# I2C_MULTIPLEX.net
KiCad netlist of a schematic drawn in Altium Designer
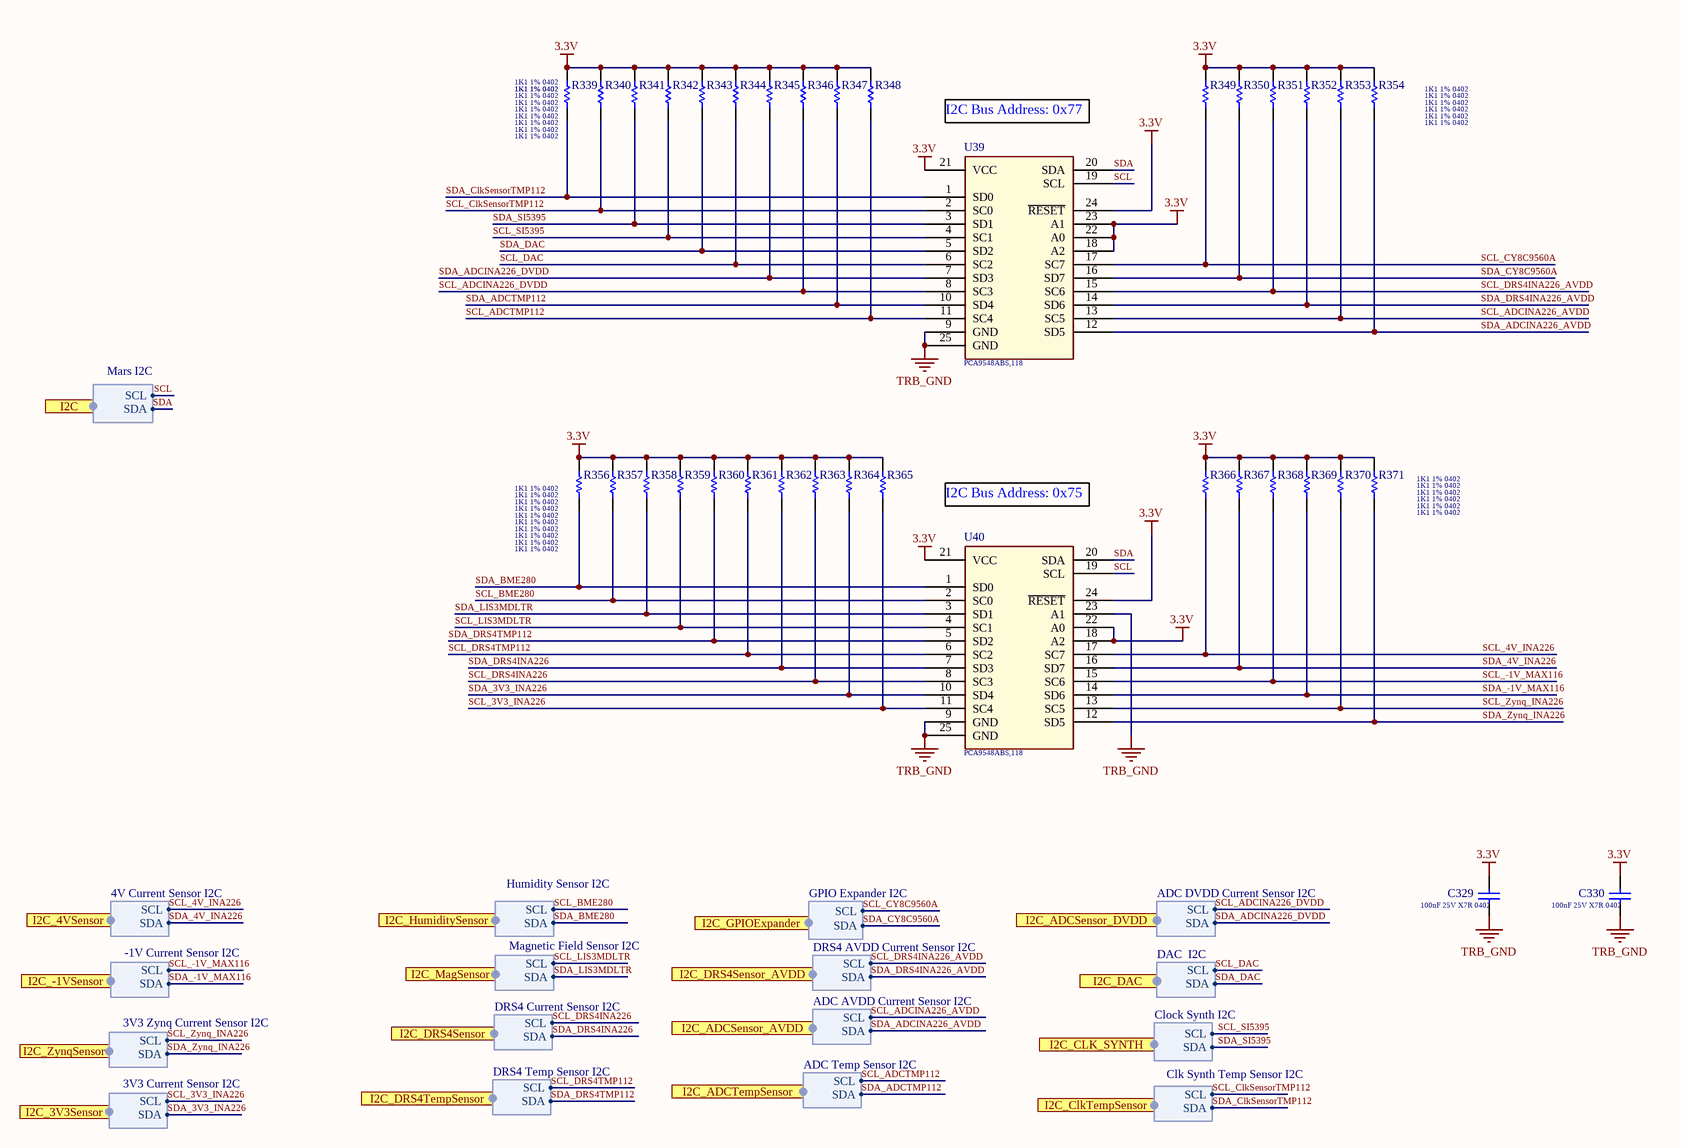
[diagram p0: I2C_MULTIPLEX.SchDoc]

(export (version "E")
  (design (tool "Eeschema 10.0.6"))
  (components
    (comp (ref "C329")
      (value "Cap_Taiyo_Yuden_TMK105B7104KV-FR_100nF")
      (footprint "Cap_Taiyo_Yuden_TMK105B7104KV-FR_100nF")
      (description "CAP CER 100nF 25V X7R 0402")
      (fields (field (name "CAPACITANCE") "100nF 25V X7R 0402"))
      (libsource (lib "Cap_Taiyo_Yuden_TMK105B7104KV-FR_100nF") (part "Cap_Taiyo_Yuden_TMK105B7104KV-FR_100nF"))
    )
    (comp (ref "C330")
      (value "Cap_Taiyo_Yuden_TMK105B7104KV-FR_100nF")
      (footprint "Cap_Taiyo_Yuden_TMK105B7104KV-FR_100nF")
      (description "CAP CER 100nF 25V X7R 0402")
      (fields (field (name "CAPACITANCE") "100nF 25V X7R 0402"))
      (libsource (lib "Cap_Taiyo_Yuden_TMK105B7104KV-FR_100nF") (part "Cap_Taiyo_Yuden_TMK105B7104KV-FR_100nF"))
    )
    (comp (ref "R339")
      (value "1K1 1% 0402")
      (footprint "RESC0402(1005)_L")
      (description "1K1 0.063W 1% 0402 (1005 Metric)  SMD")
      (fields (field (name "POWER") "0.063 W") (field (name "TOLERANCE") "1 %"))
      (libsource (lib "Altium Content Vault") (part "RES"))
    )
    (comp (ref "R340")
      (value "1K1 1% 0402")
      (footprint "RESC0402(1005)_L")
      (description "1K1 0.063W 1% 0402 (1005 Metric)  SMD")
      (fields (field (name "POWER") "0.063 W") (field (name "TOLERANCE") "1 %"))
      (libsource (lib "Altium Content Vault") (part "RES"))
    )
    (comp (ref "R341")
      (value "1K1 1% 0402")
      (footprint "RESC0402(1005)_L")
      (description "1K1 0.063W 1% 0402 (1005 Metric)  SMD")
      (fields (field (name "POWER") "0.063 W") (field (name "TOLERANCE") "1 %"))
      (libsource (lib "Altium Content Vault") (part "RES"))
    )
    (comp (ref "R342")
      (value "1K1 1% 0402")
      (footprint "RESC0402(1005)_L")
      (description "1K1 0.063W 1% 0402 (1005 Metric)  SMD")
      (fields (field (name "POWER") "0.063 W") (field (name "TOLERANCE") "1 %"))
      (libsource (lib "Altium Content Vault") (part "RES"))
    )
    (comp (ref "R343")
      (value "1K1 1% 0402")
      (footprint "RESC0402(1005)_L")
      (description "1K1 0.063W 1% 0402 (1005 Metric)  SMD")
      (fields (field (name "POWER") "0.063 W") (field (name "TOLERANCE") "1 %"))
      (libsource (lib "Altium Content Vault") (part "RES"))
    )
    (comp (ref "R344")
      (value "1K1 1% 0402")
      (footprint "RESC0402(1005)_L")
      (description "1K1 0.063W 1% 0402 (1005 Metric)  SMD")
      (fields (field (name "POWER") "0.063 W") (field (name "TOLERANCE") "1 %"))
      (libsource (lib "Altium Content Vault") (part "RES"))
    )
    (comp (ref "R345")
      (value "1K1 1% 0402")
      (footprint "RESC0402(1005)_L")
      (description "1K1 0.063W 1% 0402 (1005 Metric)  SMD")
      (fields (field (name "POWER") "0.063 W") (field (name "TOLERANCE") "1 %"))
      (libsource (lib "Altium Content Vault") (part "RES"))
    )
    (comp (ref "R346")
      (value "1K1 1% 0402")
      (footprint "RESC0402(1005)_L")
      (description "1K1 0.063W 1% 0402 (1005 Metric)  SMD")
      (fields (field (name "POWER") "0.063 W") (field (name "TOLERANCE") "1 %"))
      (libsource (lib "Altium Content Vault") (part "RES"))
    )
    (comp (ref "R347")
      (value "1K1 1% 0402")
      (footprint "RESC0402(1005)_L")
      (description "1K1 0.063W 1% 0402 (1005 Metric)  SMD")
      (fields (field (name "POWER") "0.063 W") (field (name "TOLERANCE") "1 %"))
      (libsource (lib "Altium Content Vault") (part "RES"))
    )
    (comp (ref "R348")
      (value "1K1 1% 0402")
      (footprint "RESC0402(1005)_L")
      (description "1K1 0.063W 1% 0402 (1005 Metric)  SMD")
      (fields (field (name "POWER") "0.063 W") (field (name "TOLERANCE") "1 %"))
      (libsource (lib "Altium Content Vault") (part "RES"))
    )
    (comp (ref "R349")
      (value "1K1 1% 0402")
      (footprint "RESC0402(1005)_L")
      (description "1K1 0.063W 1% 0402 (1005 Metric)  SMD")
      (fields (field (name "POWER") "0.063 W") (field (name "TOLERANCE") "1 %"))
      (libsource (lib "Altium Content Vault") (part "RES"))
    )
    (comp (ref "R350")
      (value "1K1 1% 0402")
      (footprint "RESC0402(1005)_L")
      (description "1K1 0.063W 1% 0402 (1005 Metric)  SMD")
      (fields (field (name "POWER") "0.063 W") (field (name "TOLERANCE") "1 %"))
      (libsource (lib "Altium Content Vault") (part "RES"))
    )
    (comp (ref "R351")
      (value "1K1 1% 0402")
      (footprint "RESC0402(1005)_L")
      (description "1K1 0.063W 1% 0402 (1005 Metric)  SMD")
      (fields (field (name "POWER") "0.063 W") (field (name "TOLERANCE") "1 %"))
      (libsource (lib "Altium Content Vault") (part "RES"))
    )
    (comp (ref "R352")
      (value "1K1 1% 0402")
      (footprint "RESC0402(1005)_L")
      (description "1K1 0.063W 1% 0402 (1005 Metric)  SMD")
      (fields (field (name "POWER") "0.063 W") (field (name "TOLERANCE") "1 %"))
      (libsource (lib "Altium Content Vault") (part "RES"))
    )
    (comp (ref "R353")
      (value "1K1 1% 0402")
      (footprint "RESC0402(1005)_L")
      (description "1K1 0.063W 1% 0402 (1005 Metric)  SMD")
      (fields (field (name "POWER") "0.063 W") (field (name "TOLERANCE") "1 %"))
      (libsource (lib "Altium Content Vault") (part "RES"))
    )
    (comp (ref "R354")
      (value "1K1 1% 0402")
      (footprint "RESC0402(1005)_L")
      (description "1K1 0.063W 1% 0402 (1005 Metric)  SMD")
      (fields (field (name "POWER") "0.063 W") (field (name "TOLERANCE") "1 %"))
      (libsource (lib "Altium Content Vault") (part "RES"))
    )
    (comp (ref "R356")
      (value "1K1 1% 0402")
      (footprint "RESC0402(1005)_L")
      (description "1K1 0.063W 1% 0402 (1005 Metric)  SMD")
      (fields (field (name "POWER") "0.063 W") (field (name "TOLERANCE") "1 %"))
      (libsource (lib "Altium Content Vault") (part "RES"))
    )
    (comp (ref "R357")
      (value "1K1 1% 0402")
      (footprint "RESC0402(1005)_L")
      (description "1K1 0.063W 1% 0402 (1005 Metric)  SMD")
      (fields (field (name "POWER") "0.063 W") (field (name "TOLERANCE") "1 %"))
      (libsource (lib "Altium Content Vault") (part "RES"))
    )
    (comp (ref "R358")
      (value "1K1 1% 0402")
      (footprint "RESC0402(1005)_L")
      (description "1K1 0.063W 1% 0402 (1005 Metric)  SMD")
      (fields (field (name "POWER") "0.063 W") (field (name "TOLERANCE") "1 %"))
      (libsource (lib "Altium Content Vault") (part "RES"))
    )
    (comp (ref "R359")
      (value "1K1 1% 0402")
      (footprint "RESC0402(1005)_L")
      (description "1K1 0.063W 1% 0402 (1005 Metric)  SMD")
      (fields (field (name "POWER") "0.063 W") (field (name "TOLERANCE") "1 %"))
      (libsource (lib "Altium Content Vault") (part "RES"))
    )
    (comp (ref "R360")
      (value "1K1 1% 0402")
      (footprint "RESC0402(1005)_L")
      (description "1K1 0.063W 1% 0402 (1005 Metric)  SMD")
      (fields (field (name "POWER") "0.063 W") (field (name "TOLERANCE") "1 %"))
      (libsource (lib "Altium Content Vault") (part "RES"))
    )
    (comp (ref "R361")
      (value "1K1 1% 0402")
      (footprint "RESC0402(1005)_L")
      (description "1K1 0.063W 1% 0402 (1005 Metric)  SMD")
      (fields (field (name "POWER") "0.063 W") (field (name "TOLERANCE") "1 %"))
      (libsource (lib "Altium Content Vault") (part "RES"))
    )
    (comp (ref "R362")
      (value "1K1 1% 0402")
      (footprint "RESC0402(1005)_L")
      (description "1K1 0.063W 1% 0402 (1005 Metric)  SMD")
      (fields (field (name "POWER") "0.063 W") (field (name "TOLERANCE") "1 %"))
      (libsource (lib "Altium Content Vault") (part "RES"))
    )
    (comp (ref "R363")
      (value "1K1 1% 0402")
      (footprint "RESC0402(1005)_L")
      (description "1K1 0.063W 1% 0402 (1005 Metric)  SMD")
      (fields (field (name "POWER") "0.063 W") (field (name "TOLERANCE") "1 %"))
      (libsource (lib "Altium Content Vault") (part "RES"))
    )
    (comp (ref "R364")
      (value "1K1 1% 0402")
      (footprint "RESC0402(1005)_L")
      (description "1K1 0.063W 1% 0402 (1005 Metric)  SMD")
      (fields (field (name "POWER") "0.063 W") (field (name "TOLERANCE") "1 %"))
      (libsource (lib "Altium Content Vault") (part "RES"))
    )
    (comp (ref "R365")
      (value "1K1 1% 0402")
      (footprint "RESC0402(1005)_L")
      (description "1K1 0.063W 1% 0402 (1005 Metric)  SMD")
      (fields (field (name "POWER") "0.063 W") (field (name "TOLERANCE") "1 %"))
      (libsource (lib "Altium Content Vault") (part "RES"))
    )
    (comp (ref "R366")
      (value "1K1 1% 0402")
      (footprint "RESC0402(1005)_L")
      (description "1K1 0.063W 1% 0402 (1005 Metric)  SMD")
      (fields (field (name "POWER") "0.063 W") (field (name "TOLERANCE") "1 %"))
      (libsource (lib "Altium Content Vault") (part "RES"))
    )
    (comp (ref "R367")
      (value "1K1 1% 0402")
      (footprint "RESC0402(1005)_L")
      (description "1K1 0.063W 1% 0402 (1005 Metric)  SMD")
      (fields (field (name "POWER") "0.063 W") (field (name "TOLERANCE") "1 %"))
      (libsource (lib "Altium Content Vault") (part "RES"))
    )
    (comp (ref "R368")
      (value "1K1 1% 0402")
      (footprint "RESC0402(1005)_L")
      (description "1K1 0.063W 1% 0402 (1005 Metric)  SMD")
      (fields (field (name "POWER") "0.063 W") (field (name "TOLERANCE") "1 %"))
      (libsource (lib "Altium Content Vault") (part "RES"))
    )
    (comp (ref "R369")
      (value "1K1 1% 0402")
      (footprint "RESC0402(1005)_L")
      (description "1K1 0.063W 1% 0402 (1005 Metric)  SMD")
      (fields (field (name "POWER") "0.063 W") (field (name "TOLERANCE") "1 %"))
      (libsource (lib "Altium Content Vault") (part "RES"))
    )
    (comp (ref "R370")
      (value "1K1 1% 0402")
      (footprint "RESC0402(1005)_L")
      (description "1K1 0.063W 1% 0402 (1005 Metric)  SMD")
      (fields (field (name "POWER") "0.063 W") (field (name "TOLERANCE") "1 %"))
      (libsource (lib "Altium Content Vault") (part "RES"))
    )
    (comp (ref "R371")
      (value "1K1 1% 0402")
      (footprint "RESC0402(1005)_L")
      (description "1K1 0.063W 1% 0402 (1005 Metric)  SMD")
      (fields (field (name "POWER") "0.063 W") (field (name "TOLERANCE") "1 %"))
      (libsource (lib "Altium Content Vault") (part "RES"))
    )
    (comp (ref "U39")
      (value "IC_NXP_PCA9548ABS,118_I2C_8Channel")
      (footprint "IC_NXP_PCA9548ABS,118_I2C_8Channel")
      (description "Multiplexer Switch ICs 8CH I2C SWTCH W/REST")
      (fields (field (name "SERIES") "PCA9548ABS,118"))
      (libsource (lib "IC_NXP_PCA9548ABS,118_I2C_8Channel") (part "IC_NXP_PCA9548ABS,118_I2C_8Channel"))
    )
    (comp (ref "U40")
      (value "IC_NXP_PCA9548ABS,118_I2C_8Channel")
      (footprint "IC_NXP_PCA9548ABS,118_I2C_8Channel")
      (description "Multiplexer Switch ICs 8CH I2C SWTCH W/REST")
      (fields (field (name "SERIES") "PCA9548ABS,118"))
      (libsource (lib "IC_NXP_PCA9548ABS,118_I2C_8Channel") (part "IC_NXP_PCA9548ABS,118_I2C_8Channel"))
    )
  )
  (nets
    (net (code "23") (name "/SCL") (class "Default")
      (node (ref "U39") (pin "19") (pinfunction "SCL_19") (pintype "passive"))
      (node (ref "U40") (pin "19") (pinfunction "SCL_19") (pintype "passive"))
    )
    (net (code "24") (name "/SCL_-1V_MAX116") (class "Default")
      (node (ref "R368") (pin "1") (pinfunction "1_1") (pintype "passive"))
      (node (ref "U40") (pin "15") (pinfunction "SC6_15") (pintype "passive"))
    )
    (net (code "25") (name "/SCL_3V3_INA226") (class "Default")
      (node (ref "R365") (pin "1") (pinfunction "1_1") (pintype "passive"))
      (node (ref "U40") (pin "11") (pinfunction "SC4_11") (pintype "passive"))
    )
    (net (code "26") (name "/SCL_4V_INA226") (class "Default")
      (node (ref "R366") (pin "1") (pinfunction "1_1") (pintype "passive"))
      (node (ref "U40") (pin "17") (pinfunction "SC7_17") (pintype "passive"))
    )
    (net (code "27") (name "/SCL_ADCINA226_AVDD") (class "Default")
      (node (ref "R353") (pin "1") (pinfunction "1_1") (pintype "passive"))
      (node (ref "U39") (pin "13") (pinfunction "SC5_13") (pintype "passive"))
    )
    (net (code "28") (name "/SCL_ADCINA226_DVDD") (class "Default")
      (node (ref "R346") (pin "1") (pinfunction "1_1") (pintype "passive"))
      (node (ref "U39") (pin "8") (pinfunction "SC3_8") (pintype "passive"))
    )
    (net (code "29") (name "/SCL_ADCTMP112") (class "Default")
      (node (ref "R348") (pin "1") (pinfunction "1_1") (pintype "passive"))
      (node (ref "U39") (pin "11") (pinfunction "SC4_11") (pintype "passive"))
    )
    (net (code "30") (name "/SCL_BME280") (class "Default")
      (node (ref "R357") (pin "1") (pinfunction "1_1") (pintype "passive"))
      (node (ref "U40") (pin "2") (pinfunction "SC0_2") (pintype "passive"))
    )
    (net (code "31") (name "/SCL_CY8C9560A") (class "Default")
      (node (ref "R349") (pin "1") (pinfunction "1_1") (pintype "passive"))
      (node (ref "U39") (pin "17") (pinfunction "SC7_17") (pintype "passive"))
    )
    (net (code "32") (name "/SCL_ClkSensorTMP112") (class "Default")
      (node (ref "R340") (pin "1") (pinfunction "1_1") (pintype "passive"))
      (node (ref "U39") (pin "2") (pinfunction "SC0_2") (pintype "passive"))
    )
    (net (code "33") (name "/SCL_DAC") (class "Default")
      (node (ref "R344") (pin "1") (pinfunction "1_1") (pintype "passive"))
      (node (ref "U39") (pin "6") (pinfunction "SC2_6") (pintype "passive"))
    )
    (net (code "34") (name "/SCL_DRS4INA226") (class "Default")
      (node (ref "R363") (pin "1") (pinfunction "1_1") (pintype "passive"))
      (node (ref "U40") (pin "8") (pinfunction "SC3_8") (pintype "passive"))
    )
    (net (code "35") (name "/SCL_DRS4INA226_AVDD") (class "Default")
      (node (ref "R351") (pin "1") (pinfunction "1_1") (pintype "passive"))
      (node (ref "U39") (pin "15") (pinfunction "SC6_15") (pintype "passive"))
    )
    (net (code "36") (name "/SCL_DRS4TMP112") (class "Default")
      (node (ref "R361") (pin "1") (pinfunction "1_1") (pintype "passive"))
      (node (ref "U40") (pin "6") (pinfunction "SC2_6") (pintype "passive"))
    )
    (net (code "37") (name "/SCL_LIS3MDLTR") (class "Default")
      (node (ref "R359") (pin "1") (pinfunction "1_1") (pintype "passive"))
      (node (ref "U40") (pin "4") (pinfunction "SC1_4") (pintype "passive"))
    )
    (net (code "38") (name "/SCL_SI5395") (class "Default")
      (node (ref "R342") (pin "1") (pinfunction "1_1") (pintype "passive"))
      (node (ref "U39") (pin "4") (pinfunction "SC1_4") (pintype "passive"))
    )
    (net (code "39") (name "/SCL_Zynq_INA226") (class "Default")
      (node (ref "R370") (pin "1") (pinfunction "1_1") (pintype "passive"))
      (node (ref "U40") (pin "13") (pinfunction "SC5_13") (pintype "passive"))
    )
    (net (code "40") (name "/SDA") (class "Default")
      (node (ref "U39") (pin "20") (pinfunction "SDA_20") (pintype "passive"))
      (node (ref "U40") (pin "20") (pinfunction "SDA_20") (pintype "passive"))
    )
    (net (code "41") (name "/SDA_-1V_MAX116") (class "Default")
      (node (ref "R369") (pin "1") (pinfunction "1_1") (pintype "passive"))
      (node (ref "U40") (pin "14") (pinfunction "SD6_14") (pintype "passive"))
    )
    (net (code "42") (name "/SDA_3V3_INA226") (class "Default")
      (node (ref "R364") (pin "1") (pinfunction "1_1") (pintype "passive"))
      (node (ref "U40") (pin "10") (pinfunction "SD4_10") (pintype "passive"))
    )
    (net (code "43") (name "/SDA_4V_INA226") (class "Default")
      (node (ref "R367") (pin "1") (pinfunction "1_1") (pintype "passive"))
      (node (ref "U40") (pin "16") (pinfunction "SD7_16") (pintype "passive"))
    )
    (net (code "44") (name "/SDA_ADCINA226_AVDD") (class "Default")
      (node (ref "R354") (pin "1") (pinfunction "1_1") (pintype "passive"))
      (node (ref "U39") (pin "12") (pinfunction "SD5_12") (pintype "passive"))
    )
    (net (code "45") (name "/SDA_ADCINA226_DVDD") (class "Default")
      (node (ref "R345") (pin "1") (pinfunction "1_1") (pintype "passive"))
      (node (ref "U39") (pin "7") (pinfunction "SD3_7") (pintype "passive"))
    )
    (net (code "46") (name "/SDA_ADCTMP112") (class "Default")
      (node (ref "R347") (pin "1") (pinfunction "1_1") (pintype "passive"))
      (node (ref "U39") (pin "10") (pinfunction "SD4_10") (pintype "passive"))
    )
    (net (code "47") (name "/SDA_BME280") (class "Default")
      (node (ref "R356") (pin "1") (pinfunction "1_1") (pintype "passive"))
      (node (ref "U40") (pin "1") (pinfunction "SD0_1") (pintype "passive"))
    )
    (net (code "48") (name "/SDA_CY8C9560A") (class "Default")
      (node (ref "R350") (pin "1") (pinfunction "1_1") (pintype "passive"))
      (node (ref "U39") (pin "16") (pinfunction "SD7_16") (pintype "passive"))
    )
    (net (code "49") (name "/SDA_ClkSensorTMP112") (class "Default")
      (node (ref "R339") (pin "1") (pinfunction "1_1") (pintype "passive"))
      (node (ref "U39") (pin "1") (pinfunction "SD0_1") (pintype "passive"))
    )
    (net (code "50") (name "/SDA_DAC") (class "Default")
      (node (ref "R343") (pin "1") (pinfunction "1_1") (pintype "passive"))
      (node (ref "U39") (pin "5") (pinfunction "SD2_5") (pintype "passive"))
    )
    (net (code "51") (name "/SDA_DRS4INA226") (class "Default")
      (node (ref "R362") (pin "1") (pinfunction "1_1") (pintype "passive"))
      (node (ref "U40") (pin "7") (pinfunction "SD3_7") (pintype "passive"))
    )
    (net (code "52") (name "/SDA_DRS4INA226_AVDD") (class "Default")
      (node (ref "R352") (pin "1") (pinfunction "1_1") (pintype "passive"))
      (node (ref "U39") (pin "14") (pinfunction "SD6_14") (pintype "passive"))
    )
    (net (code "53") (name "/SDA_DRS4TMP112") (class "Default")
      (node (ref "R360") (pin "1") (pinfunction "1_1") (pintype "passive"))
      (node (ref "U40") (pin "5") (pinfunction "SD2_5") (pintype "passive"))
    )
    (net (code "54") (name "/SDA_LIS3MDLTR") (class "Default")
      (node (ref "R358") (pin "1") (pinfunction "1_1") (pintype "passive"))
      (node (ref "U40") (pin "3") (pinfunction "SD1_3") (pintype "passive"))
    )
    (net (code "55") (name "/SDA_SI5395") (class "Default")
      (node (ref "R341") (pin "1") (pinfunction "1_1") (pintype "passive"))
      (node (ref "U39") (pin "3") (pinfunction "SD1_3") (pintype "passive"))
    )
    (net (code "56") (name "/SDA_Zynq_INA226") (class "Default")
      (node (ref "R371") (pin "1") (pinfunction "1_1") (pintype "passive"))
      (node (ref "U40") (pin "12") (pinfunction "SD5_12") (pintype "passive"))
    )
    (net (code "74") (name "3.3V") (class "Default")
      (node (ref "C329") (pin "2") (pinfunction "2_2") (pintype "passive"))
      (node (ref "C330") (pin "2") (pinfunction "2_2") (pintype "passive"))
      (node (ref "R339") (pin "2") (pinfunction "2_2") (pintype "passive"))
      (node (ref "R340") (pin "2") (pinfunction "2_2") (pintype "passive"))
      (node (ref "R341") (pin "2") (pinfunction "2_2") (pintype "passive"))
      (node (ref "R342") (pin "2") (pinfunction "2_2") (pintype "passive"))
      (node (ref "R343") (pin "2") (pinfunction "2_2") (pintype "passive"))
      (node (ref "R344") (pin "2") (pinfunction "2_2") (pintype "passive"))
      (node (ref "R345") (pin "2") (pinfunction "2_2") (pintype "passive"))
      (node (ref "R346") (pin "2") (pinfunction "2_2") (pintype "passive"))
      (node (ref "R347") (pin "2") (pinfunction "2_2") (pintype "passive"))
      (node (ref "R348") (pin "2") (pinfunction "2_2") (pintype "passive"))
      (node (ref "R349") (pin "2") (pinfunction "2_2") (pintype "passive"))
      (node (ref "R350") (pin "2") (pinfunction "2_2") (pintype "passive"))
      (node (ref "R351") (pin "2") (pinfunction "2_2") (pintype "passive"))
      (node (ref "R352") (pin "2") (pinfunction "2_2") (pintype "passive"))
      (node (ref "R353") (pin "2") (pinfunction "2_2") (pintype "passive"))
      (node (ref "R354") (pin "2") (pinfunction "2_2") (pintype "passive"))
      (node (ref "R356") (pin "2") (pinfunction "2_2") (pintype "passive"))
      (node (ref "R357") (pin "2") (pinfunction "2_2") (pintype "passive"))
      (node (ref "R358") (pin "2") (pinfunction "2_2") (pintype "passive"))
      (node (ref "R359") (pin "2") (pinfunction "2_2") (pintype "passive"))
      (node (ref "R360") (pin "2") (pinfunction "2_2") (pintype "passive"))
      (node (ref "R361") (pin "2") (pinfunction "2_2") (pintype "passive"))
      (node (ref "R362") (pin "2") (pinfunction "2_2") (pintype "passive"))
      (node (ref "R363") (pin "2") (pinfunction "2_2") (pintype "passive"))
      (node (ref "R364") (pin "2") (pinfunction "2_2") (pintype "passive"))
      (node (ref "R365") (pin "2") (pinfunction "2_2") (pintype "passive"))
      (node (ref "R366") (pin "2") (pinfunction "2_2") (pintype "passive"))
      (node (ref "R367") (pin "2") (pinfunction "2_2") (pintype "passive"))
      (node (ref "R368") (pin "2") (pinfunction "2_2") (pintype "passive"))
      (node (ref "R369") (pin "2") (pinfunction "2_2") (pintype "passive"))
      (node (ref "R370") (pin "2") (pinfunction "2_2") (pintype "passive"))
      (node (ref "R371") (pin "2") (pinfunction "2_2") (pintype "passive"))
      (node (ref "U39") (pin "18") (pinfunction "A2_18") (pintype "passive"))
      (node (ref "U39") (pin "21") (pinfunction "VCC_21") (pintype "passive"))
      (node (ref "U39") (pin "22") (pinfunction "A0_22") (pintype "passive"))
      (node (ref "U39") (pin "23") (pinfunction "A1_23") (pintype "passive"))
      (node (ref "U39") (pin "24") (pinfunction "~{RESET}_24") (pintype "passive"))
      (node (ref "U40") (pin "18") (pinfunction "A2_18") (pintype "passive"))
      (node (ref "U40") (pin "21") (pinfunction "VCC_21") (pintype "passive"))
      (node (ref "U40") (pin "22") (pinfunction "A0_22") (pintype "passive"))
      (node (ref "U40") (pin "24") (pinfunction "~{RESET}_24") (pintype "passive"))
    )
    (net (code "75") (name "TRB_GND") (class "Default")
      (node (ref "C329") (pin "1") (pinfunction "1_1") (pintype "passive"))
      (node (ref "C330") (pin "1") (pinfunction "1_1") (pintype "passive"))
      (node (ref "U39") (pin "25") (pinfunction "GND_25") (pintype "passive"))
      (node (ref "U39") (pin "9") (pinfunction "GND_9") (pintype "passive"))
      (node (ref "U40") (pin "23") (pinfunction "A1_23") (pintype "passive"))
      (node (ref "U40") (pin "25") (pinfunction "GND_25") (pintype "passive"))
      (node (ref "U40") (pin "9") (pinfunction "GND_9") (pintype "passive"))
    )
  )
)
